# WillowModule_v2.net
KiCad netlist of a schematic drawn in EAGLE
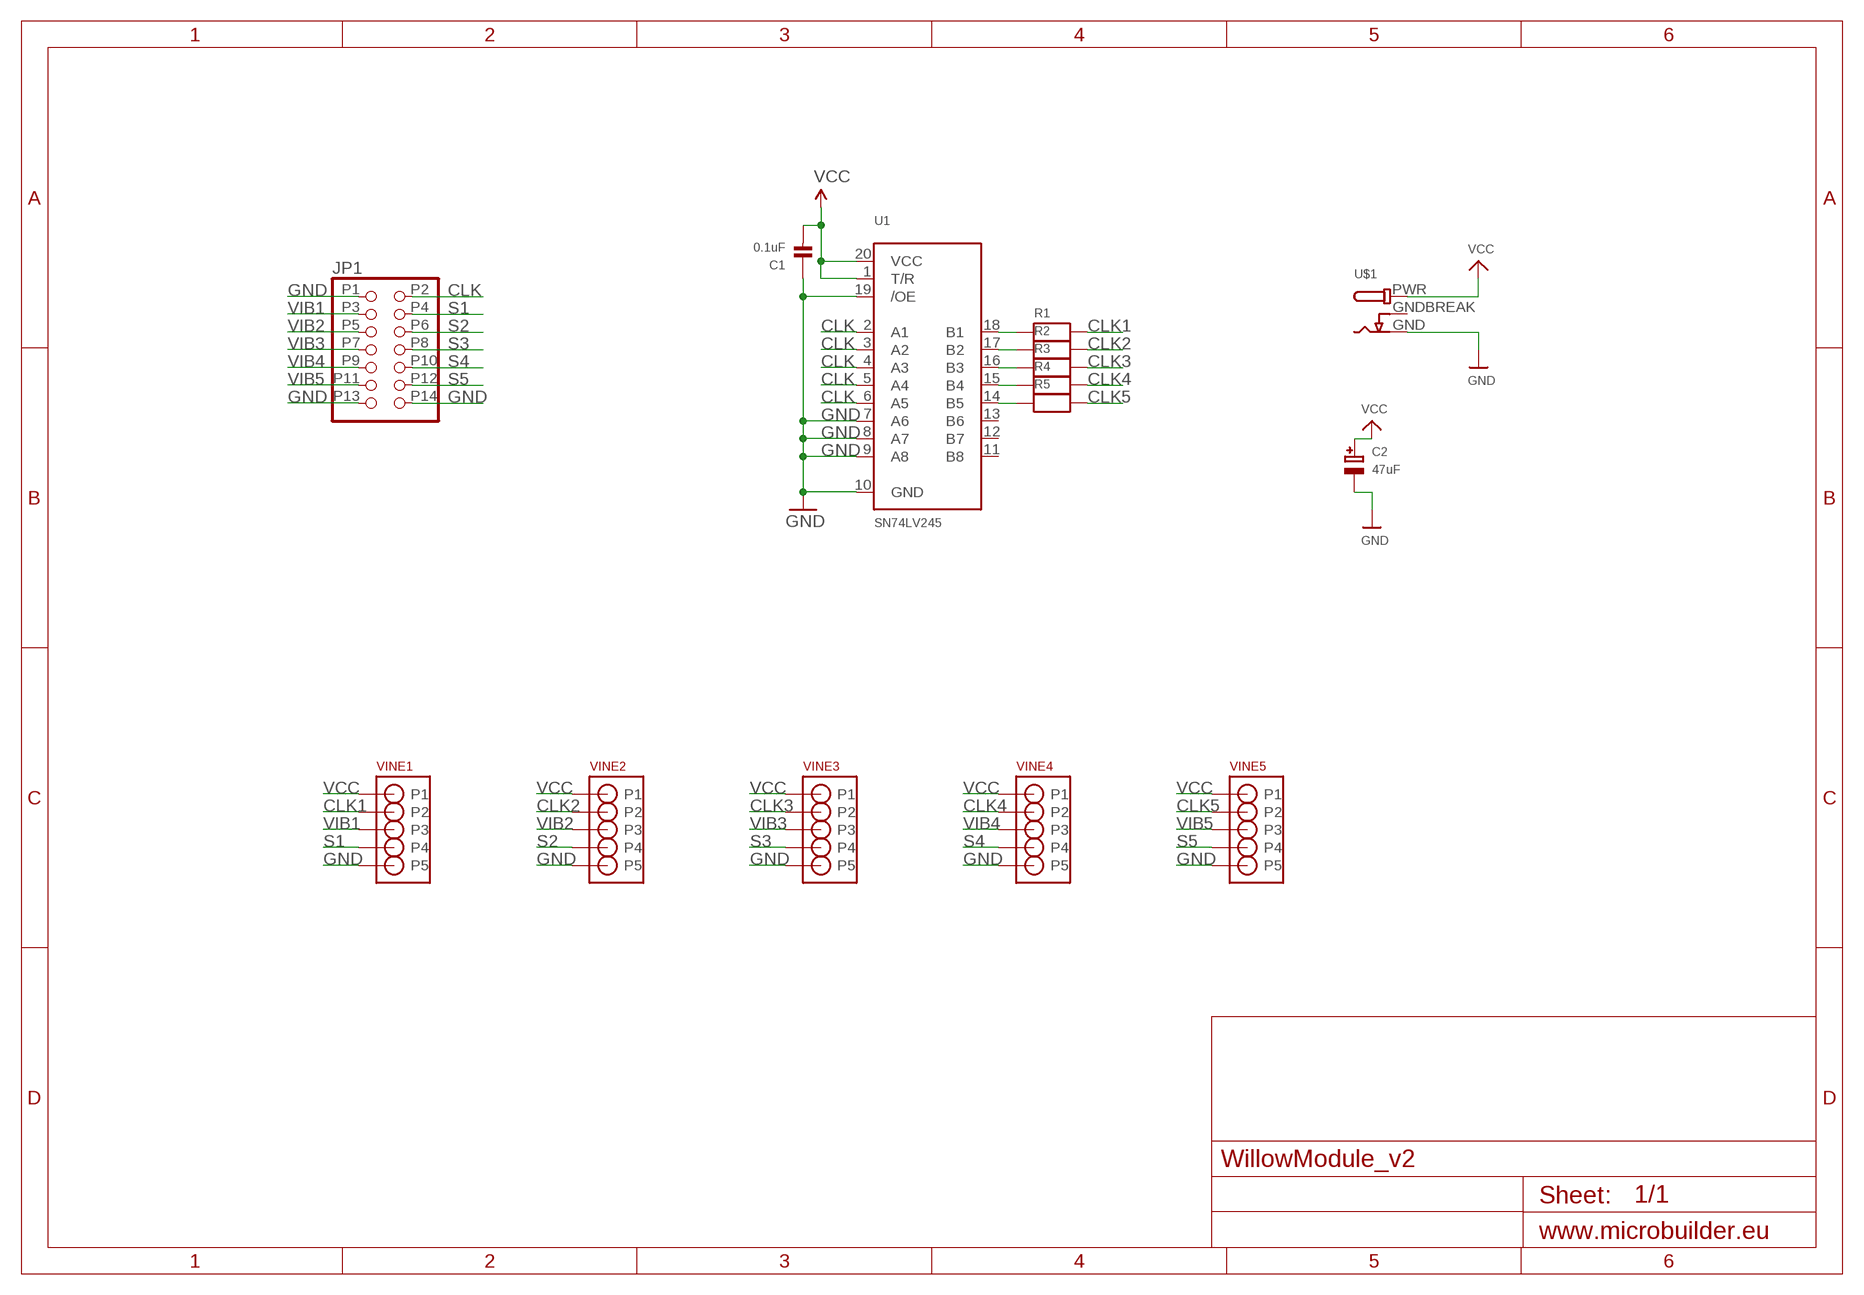
[diagram p0: schematic, sheet 1]

(export (version "E")
  (design (tool "Eeschema 10.0.6"))
  (components
    (comp (ref "C1")
      (value "0.1uF")
      (footprint "eagle-import:0603")
      (libsource (lib "eagle-import") (part "CAP_CERAMIC0603"))
    )
    (comp (ref "C2")
      (value "47uF")
      (footprint "eagle-import:PANASONIC_C")
      (libsource (lib "eagle-import") (part "CAP_ELECTROLYTICPANASONIC_C"))
    )
    (comp (ref "JP1")
      (value "IDC-BOX-HEADER")
      (footprint "eagle-import:IDC-BOX-HEADER")
      (libsource (lib "eagle-import") (part "IDC-BOX-HEADER"))
    )
    (comp (ref "R1")
      (value "RESISTOR0603")
      (footprint "eagle-import:0603")
      (libsource (lib "eagle-import") (part "RESISTOR0603"))
    )
    (comp (ref "R2")
      (value "RESISTOR0603")
      (footprint "eagle-import:0603")
      (libsource (lib "eagle-import") (part "RESISTOR0603"))
    )
    (comp (ref "R3")
      (value "RESISTOR0603")
      (footprint "eagle-import:0603")
      (libsource (lib "eagle-import") (part "RESISTOR0603"))
    )
    (comp (ref "R4")
      (value "RESISTOR0603")
      (footprint "eagle-import:0603")
      (libsource (lib "eagle-import") (part "RESISTOR0603"))
    )
    (comp (ref "R5")
      (value "RESISTOR0603")
      (footprint "eagle-import:0603")
      (libsource (lib "eagle-import") (part "RESISTOR0603"))
    )
    (comp (ref "U$1")
      (value "DC-POWER-JACK-3PIN")
      (footprint "eagle-import:PJ-050AH")
      (libsource (lib "eagle-import") (part "DC-POWER-JACK-3PIN"))
    )
    (comp (ref "U1")
      (value "SN74LV245")
      (footprint "eagle-import:TSSOP20")
      (libsource (lib "eagle-import") (part "74LCX245"))
    )
    (comp (ref "VINE1")
      (value "DIN-5PIN-180SDS-50J")
      (footprint "eagle-import:SDS-50J")
      (libsource (lib "eagle-import") (part "DIN-5PIN-180SDS-50J"))
    )
    (comp (ref "VINE2")
      (value "DIN-5PIN-180SDS-50J")
      (footprint "eagle-import:SDS-50J")
      (libsource (lib "eagle-import") (part "DIN-5PIN-180SDS-50J"))
    )
    (comp (ref "VINE3")
      (value "DIN-5PIN-180SDS-50J")
      (footprint "eagle-import:SDS-50J")
      (libsource (lib "eagle-import") (part "DIN-5PIN-180SDS-50J"))
    )
    (comp (ref "VINE4")
      (value "DIN-5PIN-180SDS-50J")
      (footprint "eagle-import:SDS-50J")
      (libsource (lib "eagle-import") (part "DIN-5PIN-180SDS-50J"))
    )
    (comp (ref "VINE5")
      (value "DIN-5PIN-180SDS-50J")
      (footprint "eagle-import:SDS-50J")
      (libsource (lib "eagle-import") (part "DIN-5PIN-180SDS-50J"))
    )
  )
  (nets
    (net (code "1") (name "/CLK") (class "Default")
      (node (ref "JP1") (pin "P2") (pinfunction "2_P2") (pintype "passive"))
      (node (ref "U1") (pin "2") (pinfunction "A1_2") (pintype "bidirectional"))
      (node (ref "U1") (pin "3") (pinfunction "A2_3") (pintype "bidirectional"))
      (node (ref "U1") (pin "4") (pinfunction "A3_4") (pintype "bidirectional"))
      (node (ref "U1") (pin "5") (pinfunction "A4_5") (pintype "bidirectional"))
      (node (ref "U1") (pin "6") (pinfunction "A5_6") (pintype "bidirectional"))
    )
    (net (code "2") (name "/CLK1") (class "Default")
      (node (ref "R1") (pin "2") (pinfunction "2_2") (pintype "passive"))
      (node (ref "VINE1") (pin "P2") (pinfunction "P2_P2") (pintype "bidirectional"))
    )
    (net (code "3") (name "/CLK2") (class "Default")
      (node (ref "R2") (pin "2") (pinfunction "2_2") (pintype "passive"))
      (node (ref "VINE2") (pin "P2") (pinfunction "P2_P2") (pintype "bidirectional"))
    )
    (net (code "4") (name "/CLK3") (class "Default")
      (node (ref "R3") (pin "2") (pinfunction "2_2") (pintype "passive"))
      (node (ref "VINE3") (pin "P2") (pinfunction "P2_P2") (pintype "bidirectional"))
    )
    (net (code "5") (name "/CLK4") (class "Default")
      (node (ref "R4") (pin "2") (pinfunction "2_2") (pintype "passive"))
      (node (ref "VINE4") (pin "P2") (pinfunction "P2_P2") (pintype "bidirectional"))
    )
    (net (code "6") (name "/CLK5") (class "Default")
      (node (ref "R5") (pin "2") (pinfunction "2_2") (pintype "passive"))
      (node (ref "VINE5") (pin "P2") (pinfunction "P2_P2") (pintype "bidirectional"))
    )
    (net (code "7") (name "/GNDBREAK") (class "Default")
      (node (ref "U$1") (pin "GNDBREAK") (pinfunction "GNDBREAK_GNDBREAK") (pintype "power_in"))
    )
    (net (code "8") (name "/S1") (class "Default")
      (node (ref "JP1") (pin "P4") (pinfunction "4_P4") (pintype "passive"))
      (node (ref "VINE1") (pin "P4") (pinfunction "P4_P4") (pintype "bidirectional"))
    )
    (net (code "9") (name "/S2") (class "Default")
      (node (ref "JP1") (pin "P6") (pinfunction "6_P6") (pintype "passive"))
      (node (ref "VINE2") (pin "P4") (pinfunction "P4_P4") (pintype "bidirectional"))
    )
    (net (code "10") (name "/S3") (class "Default")
      (node (ref "JP1") (pin "P8") (pinfunction "8_P8") (pintype "passive"))
      (node (ref "VINE3") (pin "P4") (pinfunction "P4_P4") (pintype "bidirectional"))
    )
    (net (code "11") (name "/S4") (class "Default")
      (node (ref "JP1") (pin "P10") (pinfunction "10_P10") (pintype "passive"))
      (node (ref "VINE4") (pin "P4") (pinfunction "P4_P4") (pintype "bidirectional"))
    )
    (net (code "12") (name "/S5") (class "Default")
      (node (ref "JP1") (pin "P12") (pinfunction "12_P12") (pintype "passive"))
      (node (ref "VINE5") (pin "P4") (pinfunction "P4_P4") (pintype "bidirectional"))
    )
    (net (code "13") (name "/VIB1") (class "Default")
      (node (ref "JP1") (pin "P3") (pinfunction "3_P3") (pintype "passive"))
      (node (ref "VINE1") (pin "P3") (pinfunction "P3_P3") (pintype "bidirectional"))
    )
    (net (code "14") (name "/VIB2") (class "Default")
      (node (ref "JP1") (pin "P5") (pinfunction "5_P5") (pintype "passive"))
      (node (ref "VINE2") (pin "P3") (pinfunction "P3_P3") (pintype "bidirectional"))
    )
    (net (code "15") (name "/VIB3") (class "Default")
      (node (ref "JP1") (pin "P7") (pinfunction "7_P7") (pintype "passive"))
      (node (ref "VINE3") (pin "P3") (pinfunction "P3_P3") (pintype "bidirectional"))
    )
    (net (code "16") (name "/VIB4") (class "Default")
      (node (ref "JP1") (pin "P9") (pinfunction "9_P9") (pintype "passive"))
      (node (ref "VINE4") (pin "P3") (pinfunction "P3_P3") (pintype "bidirectional"))
    )
    (net (code "17") (name "/VIB5") (class "Default")
      (node (ref "JP1") (pin "P11") (pinfunction "11_P11") (pintype "passive"))
      (node (ref "VINE5") (pin "P3") (pinfunction "P3_P3") (pintype "bidirectional"))
    )
    (net (code "18") (name "GND") (class "Default")
      (node (ref "C1") (pin "1") (pinfunction "P$1_1") (pintype "passive"))
      (node (ref "C2") (pin "-") (pinfunction "-_-") (pintype "passive"))
      (node (ref "JP1") (pin "P1") (pinfunction "1_P1") (pintype "passive"))
      (node (ref "JP1") (pin "P13") (pinfunction "13_P13") (pintype "passive"))
      (node (ref "JP1") (pin "P14") (pinfunction "14_P14") (pintype "passive"))
      (node (ref "U$1") (pin "GND") (pinfunction "GND_GND") (pintype "power_in"))
      (node (ref "U1") (pin "10") (pinfunction "GND_10") (pintype "bidirectional"))
      (node (ref "U1") (pin "19") (pinfunction "/OE_19") (pintype "bidirectional"))
      (node (ref "U1") (pin "7") (pinfunction "A6_7") (pintype "bidirectional"))
      (node (ref "U1") (pin "8") (pinfunction "A7_8") (pintype "bidirectional"))
      (node (ref "U1") (pin "9") (pinfunction "A8_9") (pintype "bidirectional"))
      (node (ref "VINE1") (pin "P5") (pinfunction "P5_P5") (pintype "bidirectional"))
      (node (ref "VINE2") (pin "P5") (pinfunction "P5_P5") (pintype "bidirectional"))
      (node (ref "VINE3") (pin "P5") (pinfunction "P5_P5") (pintype "bidirectional"))
      (node (ref "VINE4") (pin "P5") (pinfunction "P5_P5") (pintype "bidirectional"))
      (node (ref "VINE5") (pin "P5") (pinfunction "P5_P5") (pintype "bidirectional"))
    )
    (net (code "19") (name "Net-(U1-B1)") (class "Default")
      (node (ref "R1") (pin "1") (pinfunction "1_1") (pintype "passive"))
      (node (ref "U1") (pin "18") (pinfunction "B1_18") (pintype "bidirectional"))
    )
    (net (code "20") (name "Net-(U1-B2)") (class "Default")
      (node (ref "R2") (pin "1") (pinfunction "1_1") (pintype "passive"))
      (node (ref "U1") (pin "17") (pinfunction "B2_17") (pintype "bidirectional"))
    )
    (net (code "21") (name "Net-(U1-B3)") (class "Default")
      (node (ref "R3") (pin "1") (pinfunction "1_1") (pintype "passive"))
      (node (ref "U1") (pin "16") (pinfunction "B3_16") (pintype "bidirectional"))
    )
    (net (code "22") (name "Net-(U1-B4)") (class "Default")
      (node (ref "R4") (pin "1") (pinfunction "1_1") (pintype "passive"))
      (node (ref "U1") (pin "15") (pinfunction "B4_15") (pintype "bidirectional"))
    )
    (net (code "23") (name "Net-(U1-B5)") (class "Default")
      (node (ref "R5") (pin "1") (pinfunction "1_1") (pintype "passive"))
      (node (ref "U1") (pin "14") (pinfunction "B5_14") (pintype "bidirectional"))
    )
    (net (code "24") (name "VCC") (class "Default")
      (node (ref "C1") (pin "2") (pinfunction "P$2_2") (pintype "passive"))
      (node (ref "C2") (pin "+") (pinfunction "+_+") (pintype "passive"))
      (node (ref "U$1") (pin "PWR") (pinfunction "PWR_PWR") (pintype "power_in"))
      (node (ref "U1") (pin "1") (pinfunction "T/R_1") (pintype "bidirectional"))
      (node (ref "U1") (pin "20") (pinfunction "VCC_20") (pintype "bidirectional"))
      (node (ref "VINE1") (pin "P1") (pinfunction "P1_P1") (pintype "bidirectional"))
      (node (ref "VINE2") (pin "P1") (pinfunction "P1_P1") (pintype "bidirectional"))
      (node (ref "VINE3") (pin "P1") (pinfunction "P1_P1") (pintype "bidirectional"))
      (node (ref "VINE4") (pin "P1") (pinfunction "P1_P1") (pintype "bidirectional"))
      (node (ref "VINE5") (pin "P1") (pinfunction "P1_P1") (pintype "bidirectional"))
    )
    (net (code "25") (name "unconnected-(U1-B6-Pad13)") (class "Default")
      (node (ref "U1") (pin "13") (pinfunction "B6_13") (pintype "bidirectional"))
    )
    (net (code "26") (name "unconnected-(U1-B7-Pad12)") (class "Default")
      (node (ref "U1") (pin "12") (pinfunction "B7_12") (pintype "bidirectional"))
    )
    (net (code "27") (name "unconnected-(U1-B8-Pad11)") (class "Default")
      (node (ref "U1") (pin "11") (pinfunction "B8_11") (pintype "bidirectional"))
    )
  )
)
